# main.net
KiCad netlist of a schematic drawn in EAGLE
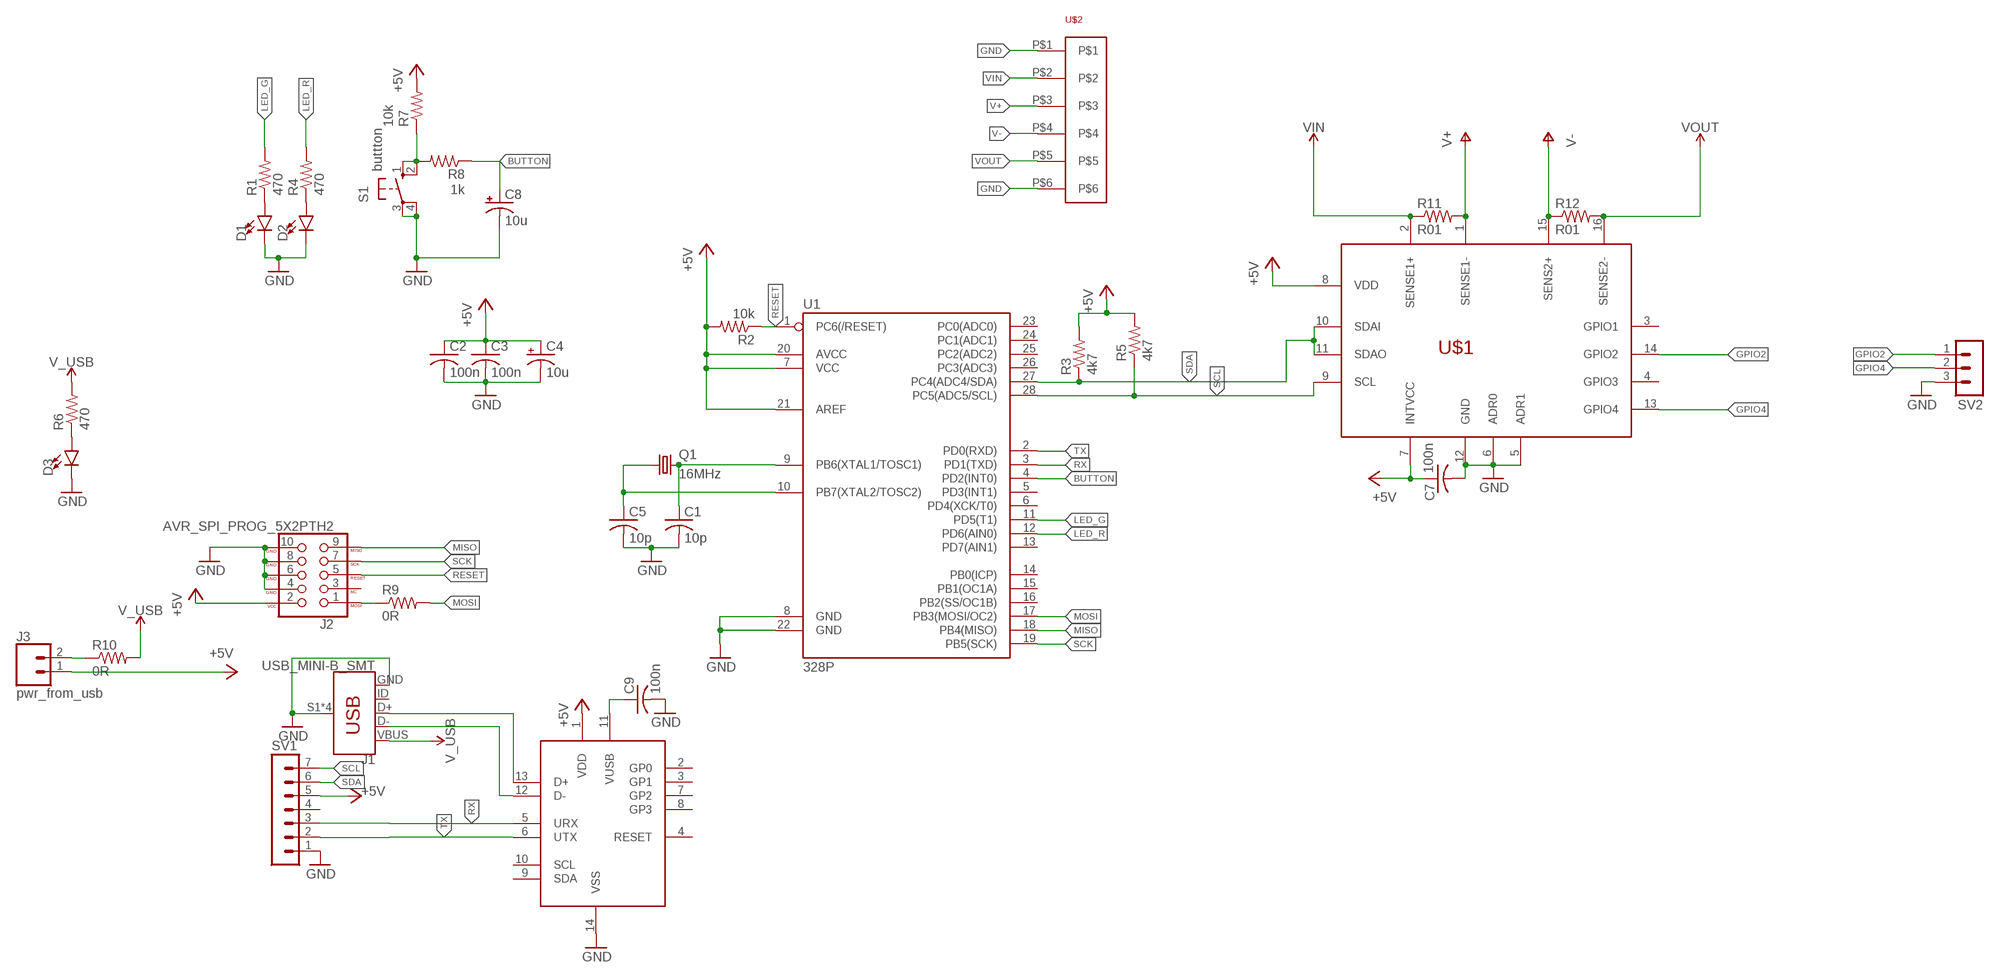
[diagram p0: schematic, sheet 1]

(export (version "E")
  (design (tool "Eeschema 10.0.6"))
  (components
    (comp (ref "BR1")
      (value "MCP2221A")
      (footprint "eagle-import:DIP14")
      (libsource (lib "eagle-import") (part "MCP2221A"))
    )
    (comp (ref "C1")
      (value "10p")
      (footprint "eagle-import:C0603")
      (libsource (lib "eagle-import") (part "C-USC0603"))
    )
    (comp (ref "C2")
      (value "100n")
      (footprint "eagle-import:C050-030X075")
      (libsource (lib "eagle-import") (part "C-US050-030X075"))
    )
    (comp (ref "C3")
      (value "100n")
      (footprint "eagle-import:C0805")
      (libsource (lib "eagle-import") (part "C-USC0805"))
    )
    (comp (ref "C4")
      (value "10u")
      (footprint "eagle-import:E2,5-6E")
      (libsource (lib "eagle-import") (part "CPOL-USE2,5-6E"))
    )
    (comp (ref "C5")
      (value "10p")
      (footprint "eagle-import:C0603")
      (libsource (lib "eagle-import") (part "C-USC0603"))
    )
    (comp (ref "C7")
      (value "100n")
      (footprint "eagle-import:C0805")
      (libsource (lib "eagle-import") (part "C-USC0805"))
    )
    (comp (ref "C8")
      (value "10u")
      (footprint "eagle-import:E5-5")
      (libsource (lib "eagle-import") (part "CPOL-USE5-5"))
    )
    (comp (ref "C9")
      (value "100n")
      (footprint "eagle-import:C050-030X075")
      (libsource (lib "eagle-import") (part "C-US050-030X075"))
    )
    (comp (ref "D1")
      (value "LED3MM")
      (footprint "eagle-import:LED_3MM")
      (libsource (lib "eagle-import") (part "LED3MM"))
    )
    (comp (ref "D2")
      (value "LED3MM")
      (footprint "eagle-import:LED_3MM")
      (libsource (lib "eagle-import") (part "LED3MM"))
    )
    (comp (ref "D3")
      (value "LED3MM")
      (footprint "eagle-import:LED_3MM")
      (libsource (lib "eagle-import") (part "LED3MM"))
    )
    (comp (ref "J1")
      (value "USB_MINI-B_SMT")
      (footprint "eagle-import:USB-MINIB")
      (libsource (lib "eagle-import") (part "USB_MINI-B_SMT"))
    )
    (comp (ref "J2")
      (value "AVR_SPI_PROG_5X2PTH2")
      (footprint "eagle-import:2X5-SHROUDED")
      (libsource (lib "eagle-import") (part "AVR_SPI_PROG_5X2PTH2"))
    )
    (comp (ref "J3")
      (value "pwr_from_usb")
      (footprint "eagle-import:1X02")
      (libsource (lib "eagle-import") (part "CONN_02"))
    )
    (comp (ref "Q1")
      (value "16MHz")
      (footprint "eagle-import:HC49U70")
      (libsource (lib "eagle-import") (part "CRYSTALHC49U70"))
    )
    (comp (ref "R1")
      (value "470")
      (footprint "eagle-import:R0805")
      (libsource (lib "eagle-import") (part "R-US_R0805"))
    )
    (comp (ref "R2")
      (value "10k")
      (footprint "eagle-import:0204_7")
      (libsource (lib "eagle-import") (part "R-US_0204/7"))
    )
    (comp (ref "R3")
      (value "4k7")
      (footprint "eagle-import:0207_10")
      (libsource (lib "eagle-import") (part "R-US_0207/10"))
    )
    (comp (ref "R4")
      (value "470")
      (footprint "eagle-import:R0805")
      (libsource (lib "eagle-import") (part "R-US_R0805"))
    )
    (comp (ref "R5")
      (value "4k7")
      (footprint "eagle-import:0207_10")
      (libsource (lib "eagle-import") (part "R-US_0207/10"))
    )
    (comp (ref "R6")
      (value "470")
      (footprint "eagle-import:R0805")
      (libsource (lib "eagle-import") (part "R-US_R0805"))
    )
    (comp (ref "R7")
      (value "10k")
      (footprint "eagle-import:R0805")
      (libsource (lib "eagle-import") (part "R-US_R0805"))
    )
    (comp (ref "R8")
      (value "1k")
      (footprint "eagle-import:R0805")
      (libsource (lib "eagle-import") (part "R-US_R0805"))
    )
    (comp (ref "R9")
      (value "0R")
      (footprint "eagle-import:0204_7")
      (libsource (lib "eagle-import") (part "R-US_0204/7"))
    )
    (comp (ref "R10")
      (value "0R")
      (footprint "eagle-import:0207_15")
      (libsource (lib "eagle-import") (part "R-US_0207/15"))
    )
    (comp (ref "R11")
      (value "R01")
      (footprint "eagle-import:R2512")
      (libsource (lib "eagle-import") (part "R-US_R2512"))
    )
    (comp (ref "R12")
      (value "R01")
      (footprint "eagle-import:R2512")
      (libsource (lib "eagle-import") (part "R-US_R2512"))
    )
    (comp (ref "S1")
      (value "buttton")
      (footprint "eagle-import:B3F-10XX")
      (fields (field (name "MPN") "B3F-1000"))
      (libsource (lib "eagle-import") (part "10-XX"))
    )
    (comp (ref "SV1")
      (value "MA07-1")
      (footprint "eagle-import:MA07-1")
      (libsource (lib "eagle-import") (part "MA07-1"))
    )
    (comp (ref "SV2")
      (value "MA03-1")
      (footprint "eagle-import:MA03-1")
      (libsource (lib "eagle-import") (part "MA03-1"))
    )
    (comp (ref "U$1")
      (value "LTC2992")
      (footprint "eagle-import:MSOP16")
      (libsource (lib "eagle-import") (part "LTC2992"))
    )
    (comp (ref "U$2")
      (value "SCREWTERM_5MM_6WAY")
      (footprint "eagle-import:SCREWTERM_5MM_6WAY")
      (libsource (lib "eagle-import") (part "SCREWTERM_5MM_6WAY"))
    )
    (comp (ref "U1")
      (value "328P")
      (footprint "eagle-import:DIP28")
      (libsource (lib "eagle-import") (part "ATMEGA328P_PDIP"))
    )
  )
  (nets
    (net (code "1") (name "+5V") (class "Default")
      (node (ref "BR1") (pin "1") (pinfunction "VDD_1") (pintype "bidirectional"))
      (node (ref "C2") (pin "1") (pinfunction "1_1") (pintype "passive"))
      (node (ref "C3") (pin "1") (pinfunction "1_1") (pintype "passive"))
      (node (ref "C4") (pin "+") (pinfunction "+_+") (pintype "passive"))
      (node (ref "C7") (pin "1") (pinfunction "1_1") (pintype "passive"))
      (node (ref "J2") (pin "2") (pinfunction "VCC_2") (pintype "power_in"))
      (node (ref "J3") (pin "1") (pinfunction "1_1") (pintype "passive"))
      (node (ref "R2") (pin "2") (pinfunction "2_2") (pintype "passive"))
      (node (ref "R3") (pin "2") (pinfunction "2_2") (pintype "passive"))
      (node (ref "R5") (pin "2") (pinfunction "2_2") (pintype "passive"))
      (node (ref "R7") (pin "2") (pinfunction "2_2") (pintype "passive"))
      (node (ref "SV1") (pin "5") (pinfunction "5_5") (pintype "passive"))
      (node (ref "U$1") (pin "7") (pinfunction "INTVCC_7") (pintype "bidirectional"))
      (node (ref "U$1") (pin "8") (pinfunction "VDD_8") (pintype "bidirectional"))
      (node (ref "U1") (pin "20") (pinfunction "AVCC_20") (pintype "bidirectional"))
      (node (ref "U1") (pin "21") (pinfunction "AREF_21") (pintype "bidirectional"))
      (node (ref "U1") (pin "7") (pinfunction "VCC_7") (pintype "bidirectional"))
    )
    (net (code "2") (name "BUTTON") (class "Default")
      (node (ref "C8") (pin "+") (pinfunction "+_+") (pintype "passive"))
      (node (ref "R8") (pin "1") (pinfunction "1_1") (pintype "passive"))
      (node (ref "U1") (pin "4") (pinfunction "PD2(INT0)_4") (pintype "bidirectional"))
    )
    (net (code "3") (name "GND") (class "Default")
      (node (ref "BR1") (pin "14") (pinfunction "VSS_14") (pintype "bidirectional"))
      (node (ref "C1") (pin "2") (pinfunction "2_2") (pintype "passive"))
      (node (ref "C2") (pin "2") (pinfunction "2_2") (pintype "passive"))
      (node (ref "C3") (pin "2") (pinfunction "2_2") (pintype "passive"))
      (node (ref "C4") (pin "-") (pinfunction "-_-") (pintype "passive"))
      (node (ref "C5") (pin "2") (pinfunction "2_2") (pintype "passive"))
      (node (ref "C7") (pin "2") (pinfunction "2_2") (pintype "passive"))
      (node (ref "C8") (pin "-") (pinfunction "-_-") (pintype "passive"))
      (node (ref "C9") (pin "2") (pinfunction "2_2") (pintype "passive"))
      (node (ref "D1") (pin "K") (pinfunction "C_K") (pintype "passive"))
      (node (ref "D2") (pin "K") (pinfunction "C_K") (pintype "passive"))
      (node (ref "D3") (pin "K") (pinfunction "C_K") (pintype "passive"))
      (node (ref "J1") (pin "GND") (pinfunction "GND_GND") (pintype "power_in"))
      (node (ref "J1") (pin "S1") (pinfunction "SHIELD_S1") (pintype "bidirectional"))
      (node (ref "J1") (pin "S2") (pinfunction "SHIELD_S2") (pintype "bidirectional"))
      (node (ref "J1") (pin "S3") (pinfunction "SHIELD_S3") (pintype "bidirectional"))
      (node (ref "J1") (pin "S4") (pinfunction "SHIELD_S4") (pintype "bidirectional"))
      (node (ref "J2") (pin "10") (pinfunction "GND_10") (pintype "power_in"))
      (node (ref "J2") (pin "4") (pinfunction "GND_4") (pintype "power_in"))
      (node (ref "J2") (pin "6") (pinfunction "GND_6") (pintype "power_in"))
      (node (ref "J2") (pin "8") (pinfunction "GND_8") (pintype "power_in"))
      (node (ref "S1") (pin "3") (pinfunction "P_3") (pintype "passive"))
      (node (ref "S1") (pin "4") (pinfunction "P1_4") (pintype "passive"))
      (node (ref "SV1") (pin "1") (pinfunction "1_1") (pintype "passive"))
      (node (ref "SV2") (pin "3") (pinfunction "3_3") (pintype "passive"))
      (node (ref "U$1") (pin "12") (pinfunction "GND_12") (pintype "bidirectional"))
      (node (ref "U$1") (pin "5") (pinfunction "ADR1_5") (pintype "bidirectional"))
      (node (ref "U$1") (pin "6") (pinfunction "ADR0_6") (pintype "bidirectional"))
      (node (ref "U$2") (pin "P$1") (pinfunction "P$1_P$1") (pintype "bidirectional"))
      (node (ref "U$2") (pin "P$6") (pinfunction "P$6_P$6") (pintype "bidirectional"))
      (node (ref "U1") (pin "22") (pinfunction "GND_22") (pintype "bidirectional"))
      (node (ref "U1") (pin "8") (pinfunction "GND_8") (pintype "bidirectional"))
    )
    (net (code "4") (name "GPIO2") (class "Default")
      (node (ref "SV2") (pin "1") (pinfunction "1_1") (pintype "passive"))
      (node (ref "U$1") (pin "14") (pinfunction "GPIO2_14") (pintype "bidirectional"))
    )
    (net (code "5") (name "GPIO4") (class "Default")
      (node (ref "SV2") (pin "2") (pinfunction "2_2") (pintype "passive"))
      (node (ref "U$1") (pin "13") (pinfunction "GPIO4_13") (pintype "bidirectional"))
    )
    (net (code "6") (name "LED_G") (class "Default")
      (node (ref "R1") (pin "2") (pinfunction "2_2") (pintype "passive"))
      (node (ref "U1") (pin "11") (pinfunction "PD5(T1)_11") (pintype "bidirectional"))
    )
    (net (code "7") (name "LED_R") (class "Default")
      (node (ref "R4") (pin "2") (pinfunction "2_2") (pintype "passive"))
      (node (ref "U1") (pin "12") (pinfunction "PD6(AIN0)_12") (pintype "bidirectional"))
    )
    (net (code "8") (name "MISO") (class "Default")
      (node (ref "J2") (pin "9") (pinfunction "MISO_9") (pintype "passive"))
      (node (ref "U1") (pin "18") (pinfunction "PB4(MISO)_18") (pintype "bidirectional"))
    )
    (net (code "9") (name "MOSI") (class "Default")
      (node (ref "R9") (pin "2") (pinfunction "2_2") (pintype "passive"))
      (node (ref "U1") (pin "17") (pinfunction "PB3(MOSI/OC2)_17") (pintype "bidirectional"))
    )
    (net (code "10") (name "Net-(BR1-D+)") (class "Default")
      (node (ref "BR1") (pin "13") (pinfunction "D+_13") (pintype "bidirectional"))
      (node (ref "J1") (pin "D+") (pinfunction "D+_D+") (pintype "bidirectional"))
    )
    (net (code "11") (name "Net-(BR1-D-)") (class "Default")
      (node (ref "BR1") (pin "12") (pinfunction "D-_12") (pintype "bidirectional"))
      (node (ref "J1") (pin "D-") (pinfunction "D-_D-") (pintype "bidirectional"))
    )
    (net (code "12") (name "Net-(BR1-VUSB)") (class "Default")
      (node (ref "BR1") (pin "11") (pinfunction "VUSB_11") (pintype "bidirectional"))
      (node (ref "C9") (pin "1") (pinfunction "1_1") (pintype "passive"))
    )
    (net (code "13") (name "Net-(D1-PadA)") (class "Default")
      (node (ref "D1") (pin "A") (pinfunction "A_A") (pintype "passive"))
      (node (ref "R1") (pin "1") (pinfunction "1_1") (pintype "passive"))
    )
    (net (code "14") (name "Net-(D2-PadA)") (class "Default")
      (node (ref "D2") (pin "A") (pinfunction "A_A") (pintype "passive"))
      (node (ref "R4") (pin "1") (pinfunction "1_1") (pintype "passive"))
    )
    (net (code "15") (name "Net-(D3-PadA)") (class "Default")
      (node (ref "D3") (pin "A") (pinfunction "A_A") (pintype "passive"))
      (node (ref "R6") (pin "1") (pinfunction "1_1") (pintype "passive"))
    )
    (net (code "16") (name "Net-(J2-MOSI)") (class "Default")
      (node (ref "J2") (pin "1") (pinfunction "MOSI_1") (pintype "passive"))
      (node (ref "R9") (pin "1") (pinfunction "1_1") (pintype "passive"))
    )
    (net (code "17") (name "Net-(J3-Pad2)") (class "Default")
      (node (ref "J3") (pin "2") (pinfunction "2_2") (pintype "passive"))
      (node (ref "R10") (pin "1") (pinfunction "1_1") (pintype "passive"))
    )
    (net (code "18") (name "Net-(S1-S)") (class "Default")
      (node (ref "R7") (pin "1") (pinfunction "1_1") (pintype "passive"))
      (node (ref "R8") (pin "2") (pinfunction "2_2") (pintype "passive"))
      (node (ref "S1") (pin "1") (pinfunction "S_1") (pintype "passive"))
      (node (ref "S1") (pin "2") (pinfunction "S1_2") (pintype "passive"))
    )
    (net (code "19") (name "Net-(U1-PB6(XTAL1{slash}TOSC1))") (class "Default")
      (node (ref "C1") (pin "1") (pinfunction "1_1") (pintype "passive"))
      (node (ref "Q1") (pin "2") (pinfunction "2_2") (pintype "passive"))
      (node (ref "U1") (pin "9") (pinfunction "PB6(XTAL1/TOSC1)_9") (pintype "bidirectional"))
    )
    (net (code "20") (name "Net-(U1-PB7(XTAL2{slash}TOSC2))") (class "Default")
      (node (ref "C5") (pin "1") (pinfunction "1_1") (pintype "passive"))
      (node (ref "Q1") (pin "1") (pinfunction "1_1") (pintype "passive"))
      (node (ref "U1") (pin "10") (pinfunction "PB7(XTAL2/TOSC2)_10") (pintype "bidirectional"))
    )
    (net (code "21") (name "RESET") (class "Default")
      (node (ref "J2") (pin "5") (pinfunction "RESET_5") (pintype "passive"))
      (node (ref "R2") (pin "1") (pinfunction "1_1") (pintype "passive"))
      (node (ref "U1") (pin "1") (pinfunction "PC6(/RESET)_1") (pintype "bidirectional"))
    )
    (net (code "22") (name "RX") (class "Default")
      (node (ref "BR1") (pin "5") (pinfunction "URX_5") (pintype "bidirectional"))
      (node (ref "SV1") (pin "3") (pinfunction "3_3") (pintype "passive"))
      (node (ref "U1") (pin "3") (pinfunction "PD1(TXD)_3") (pintype "bidirectional"))
    )
    (net (code "23") (name "SCK") (class "Default")
      (node (ref "J2") (pin "7") (pinfunction "SCK_7") (pintype "passive"))
      (node (ref "U1") (pin "19") (pinfunction "PB5(SCK)_19") (pintype "bidirectional"))
    )
    (net (code "24") (name "SCL") (class "Default")
      (node (ref "R5") (pin "1") (pinfunction "1_1") (pintype "passive"))
      (node (ref "SV1") (pin "7") (pinfunction "7_7") (pintype "passive"))
      (node (ref "U$1") (pin "9") (pinfunction "SCL_9") (pintype "bidirectional"))
      (node (ref "U1") (pin "28") (pinfunction "PC5(ADC5/SCL)_28") (pintype "bidirectional"))
    )
    (net (code "25") (name "SDA") (class "Default")
      (node (ref "R3") (pin "1") (pinfunction "1_1") (pintype "passive"))
      (node (ref "SV1") (pin "6") (pinfunction "6_6") (pintype "passive"))
      (node (ref "U$1") (pin "10") (pinfunction "SDAI_10") (pintype "bidirectional"))
      (node (ref "U$1") (pin "11") (pinfunction "SDAO_11") (pintype "bidirectional"))
      (node (ref "U1") (pin "27") (pinfunction "PC4(ADC4/SDA)_27") (pintype "bidirectional"))
    )
    (net (code "26") (name "TX") (class "Default")
      (node (ref "BR1") (pin "6") (pinfunction "UTX_6") (pintype "bidirectional"))
      (node (ref "SV1") (pin "2") (pinfunction "2_2") (pintype "passive"))
      (node (ref "U1") (pin "2") (pinfunction "PD0(RXD)_2") (pintype "bidirectional"))
    )
    (net (code "27") (name "V+") (class "Default")
      (node (ref "R11") (pin "2") (pinfunction "2_2") (pintype "passive"))
      (node (ref "U$1") (pin "1") (pinfunction "SENSE1-_1") (pintype "bidirectional"))
      (node (ref "U$2") (pin "P$3") (pinfunction "P$3_P$3") (pintype "bidirectional"))
    )
    (net (code "28") (name "V-") (class "Default")
      (node (ref "R12") (pin "1") (pinfunction "1_1") (pintype "passive"))
      (node (ref "U$1") (pin "15") (pinfunction "SENS2+_15") (pintype "bidirectional"))
      (node (ref "U$2") (pin "P$4") (pinfunction "P$4_P$4") (pintype "bidirectional"))
    )
    (net (code "29") (name "VIN") (class "Default")
      (node (ref "R11") (pin "1") (pinfunction "1_1") (pintype "passive"))
      (node (ref "U$1") (pin "2") (pinfunction "SENSE1+_2") (pintype "bidirectional"))
      (node (ref "U$2") (pin "P$2") (pinfunction "P$2_P$2") (pintype "bidirectional"))
    )
    (net (code "30") (name "VOUT") (class "Default")
      (node (ref "R12") (pin "2") (pinfunction "2_2") (pintype "passive"))
      (node (ref "U$1") (pin "16") (pinfunction "SENSE2-_16") (pintype "bidirectional"))
      (node (ref "U$2") (pin "P$5") (pinfunction "P$5_P$5") (pintype "bidirectional"))
    )
    (net (code "31") (name "V_USB") (class "Default")
      (node (ref "J1") (pin "VBUS") (pinfunction "VBUS_VBUS") (pintype "power_in"))
      (node (ref "R10") (pin "2") (pinfunction "2_2") (pintype "passive"))
      (node (ref "R6") (pin "2") (pinfunction "2_2") (pintype "passive"))
    )
    (net (code "32") (name "unconnected-(BR1-GP0-Pad2)") (class "Default")
      (node (ref "BR1") (pin "2") (pinfunction "GP0_2") (pintype "bidirectional"))
    )
    (net (code "33") (name "unconnected-(BR1-GP1-Pad3)") (class "Default")
      (node (ref "BR1") (pin "3") (pinfunction "GP1_3") (pintype "bidirectional"))
    )
    (net (code "34") (name "unconnected-(BR1-GP2-Pad7)") (class "Default")
      (node (ref "BR1") (pin "7") (pinfunction "GP2_7") (pintype "bidirectional"))
    )
    (net (code "35") (name "unconnected-(BR1-GP3-Pad8)") (class "Default")
      (node (ref "BR1") (pin "8") (pinfunction "GP3_8") (pintype "bidirectional"))
    )
    (net (code "36") (name "unconnected-(BR1-RESET-Pad4)") (class "Default")
      (node (ref "BR1") (pin "4") (pinfunction "RESET_4") (pintype "bidirectional"))
    )
    (net (code "37") (name "unconnected-(BR1-SCL-Pad10)") (class "Default")
      (node (ref "BR1") (pin "10") (pinfunction "SCL_10") (pintype "bidirectional"))
    )
    (net (code "38") (name "unconnected-(BR1-SDA-Pad9)") (class "Default")
      (node (ref "BR1") (pin "9") (pinfunction "SDA_9") (pintype "bidirectional"))
    )
    (net (code "39") (name "unconnected-(J1-PadID)") (class "Default")
      (node (ref "J1") (pin "ID") (pinfunction "ID_ID") (pintype "bidirectional"))
    )
    (net (code "40") (name "unconnected-(J2-NC-Pad3)") (class "Default")
      (node (ref "J2") (pin "3") (pinfunction "NC_3") (pintype "no_connect"))
    )
    (net (code "41") (name "unconnected-(SV1-Pad4)") (class "Default")
      (node (ref "SV1") (pin "4") (pinfunction "4_4") (pintype "passive"))
    )
    (net (code "42") (name "unconnected-(U$1-GPIO1-Pad3)") (class "Default")
      (node (ref "U$1") (pin "3") (pinfunction "GPIO1_3") (pintype "bidirectional"))
    )
    (net (code "43") (name "unconnected-(U$1-GPIO3-Pad4)") (class "Default")
      (node (ref "U$1") (pin "4") (pinfunction "GPIO3_4") (pintype "bidirectional"))
    )
    (net (code "44") (name "unconnected-(U1-PB0(ICP)-Pad14)") (class "Default")
      (node (ref "U1") (pin "14") (pinfunction "PB0(ICP)_14") (pintype "bidirectional"))
    )
    (net (code "45") (name "unconnected-(U1-PB1(OC1A)-Pad15)") (class "Default")
      (node (ref "U1") (pin "15") (pinfunction "PB1(OC1A)_15") (pintype "bidirectional"))
    )
    (net (code "46") (name "unconnected-(U1-PB2(SS{slash}OC1B)-Pad16)") (class "Default")
      (node (ref "U1") (pin "16") (pinfunction "PB2(SS/OC1B)_16") (pintype "bidirectional"))
    )
    (net (code "47") (name "unconnected-(U1-PC0(ADC0)-Pad23)") (class "Default")
      (node (ref "U1") (pin "23") (pinfunction "PC0(ADC0)_23") (pintype "bidirectional"))
    )
    (net (code "48") (name "unconnected-(U1-PC1(ADC1)-Pad24)") (class "Default")
      (node (ref "U1") (pin "24") (pinfunction "PC1(ADC1)_24") (pintype "bidirectional"))
    )
    (net (code "49") (name "unconnected-(U1-PC2(ADC2)-Pad25)") (class "Default")
      (node (ref "U1") (pin "25") (pinfunction "PC2(ADC2)_25") (pintype "bidirectional"))
    )
    (net (code "50") (name "unconnected-(U1-PC3(ADC3)-Pad26)") (class "Default")
      (node (ref "U1") (pin "26") (pinfunction "PC3(ADC3)_26") (pintype "bidirectional"))
    )
    (net (code "51") (name "unconnected-(U1-PD3(INT1)-Pad5)") (class "Default")
      (node (ref "U1") (pin "5") (pinfunction "PD3(INT1)_5") (pintype "bidirectional"))
    )
    (net (code "52") (name "unconnected-(U1-PD4(XCK{slash}T0)-Pad6)") (class "Default")
      (node (ref "U1") (pin "6") (pinfunction "PD4(XCK/T0)_6") (pintype "bidirectional"))
    )
    (net (code "53") (name "unconnected-(U1-PD7(AIN1)-Pad13)") (class "Default")
      (node (ref "U1") (pin "13") (pinfunction "PD7(AIN1)_13") (pintype "bidirectional"))
    )
  )
)
